# Sheet1.net
KiCad netlist of a schematic drawn in Altium Designer
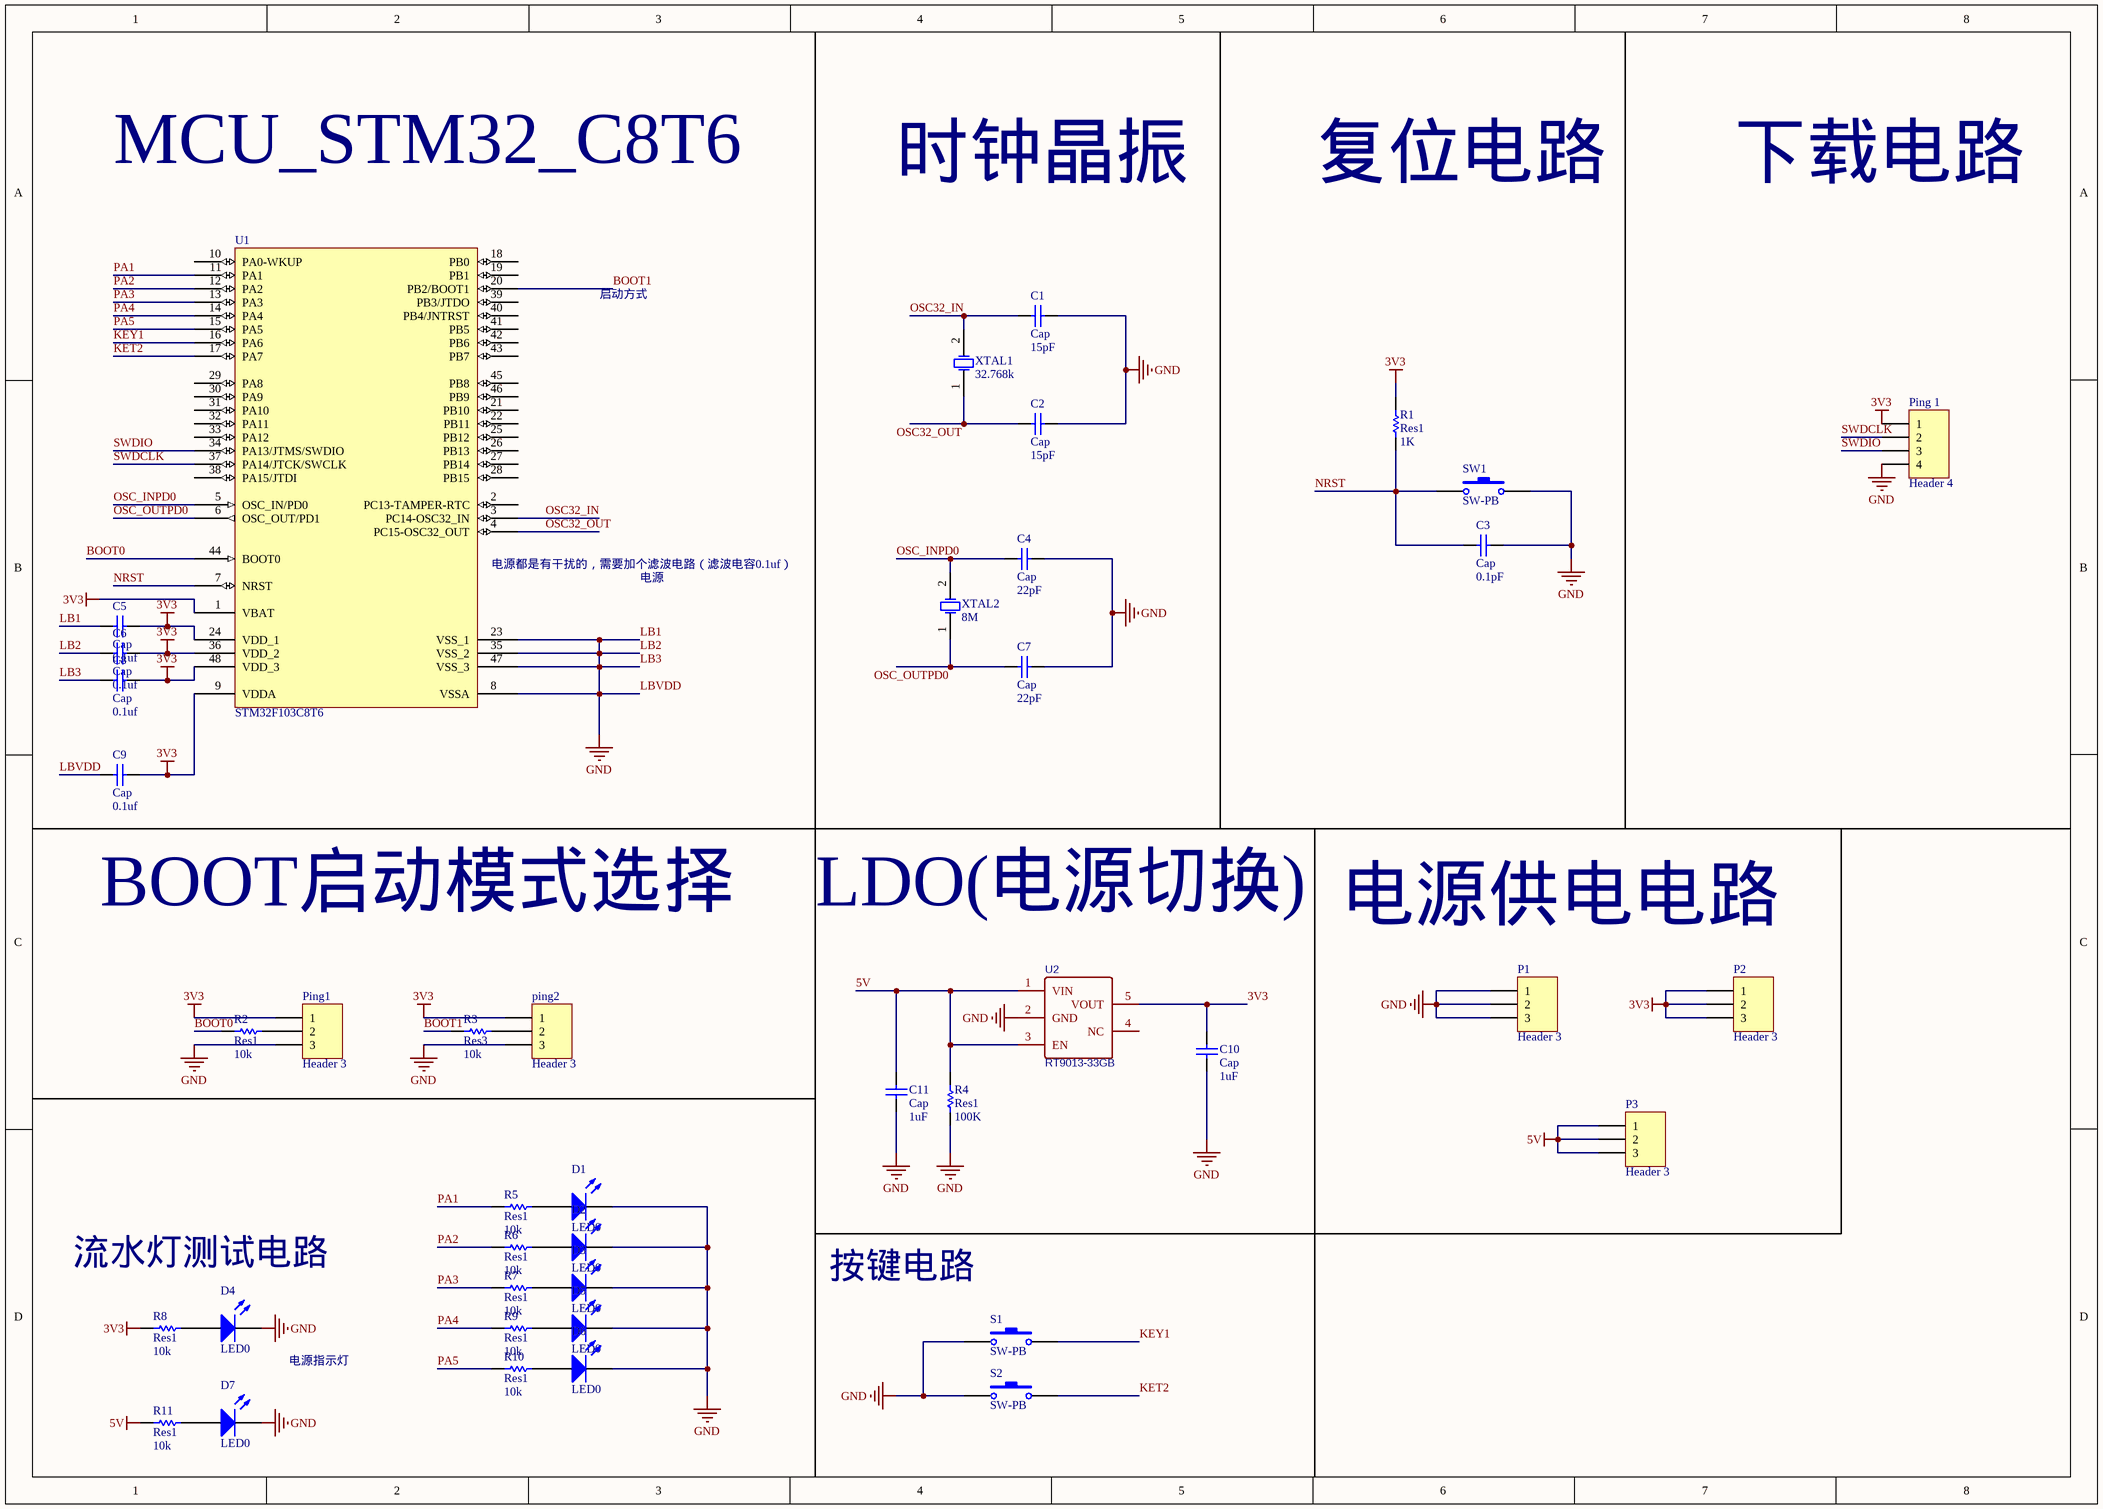
[diagram p0: Sheet1.SchDoc]

(export (version "E")
  (design (tool "Eeschema 10.0.6"))
  (components
    (comp (ref "C1")
      (value "Cap")
      (footprint "RAD-0.3")
      (description "Capacitor")
      (fields (field (name "ALTIUM_VALUE") "15pF") (field (name "PUBLISHER") "Altium Limited"))
      (libsource (lib "Miscellaneous Devices") (part "Cap"))
    )
    (comp (ref "C2")
      (value "Cap")
      (footprint "RAD-0.3")
      (description "Capacitor")
      (fields (field (name "ALTIUM_VALUE") "15pF") (field (name "PUBLISHER") "Altium Limited"))
      (libsource (lib "Miscellaneous Devices") (part "Cap"))
    )
    (comp (ref "C3")
      (value "Cap")
      (footprint "RAD-0.3")
      (description "Capacitor")
      (fields (field (name "ALTIUM_VALUE") "0.1pF") (field (name "PUBLISHER") "Altium Limited"))
      (libsource (lib "Miscellaneous Devices") (part "Cap"))
    )
    (comp (ref "C4")
      (value "Cap")
      (footprint "RAD-0.3")
      (description "Capacitor")
      (fields (field (name "ALTIUM_VALUE") "22pF") (field (name "PUBLISHER") "Altium Limited"))
      (libsource (lib "Miscellaneous Devices") (part "Cap"))
    )
    (comp (ref "C5")
      (value "Cap")
      (footprint "RAD-0.3")
      (description "Capacitor")
      (fields (field (name "ALTIUM_VALUE") "0.1uf") (field (name "PUBLISHER") "Altium Limited"))
      (libsource (lib "Miscellaneous Devices") (part "Cap"))
    )
    (comp (ref "C6")
      (value "Cap")
      (footprint "RAD-0.3")
      (description "Capacitor")
      (fields (field (name "ALTIUM_VALUE") "0.1uf") (field (name "PUBLISHER") "Altium Limited"))
      (libsource (lib "Miscellaneous Devices") (part "Cap"))
    )
    (comp (ref "C7")
      (value "Cap")
      (footprint "RAD-0.3")
      (description "Capacitor")
      (fields (field (name "ALTIUM_VALUE") "22pF") (field (name "PUBLISHER") "Altium Limited"))
      (libsource (lib "Miscellaneous Devices") (part "Cap"))
    )
    (comp (ref "C8")
      (value "Cap")
      (footprint "RAD-0.3")
      (description "Capacitor")
      (fields (field (name "ALTIUM_VALUE") "0.1uf") (field (name "PUBLISHER") "Altium Limited"))
      (libsource (lib "Miscellaneous Devices") (part "Cap"))
    )
    (comp (ref "C9")
      (value "Cap")
      (footprint "RAD-0.3")
      (description "Capacitor")
      (fields (field (name "ALTIUM_VALUE") "0.1uf") (field (name "PUBLISHER") "Altium Limited"))
      (libsource (lib "Miscellaneous Devices") (part "Cap"))
    )
    (comp (ref "C10")
      (value "Cap")
      (footprint "RAD-0.3")
      (description "Capacitor")
      (fields (field (name "ALTIUM_VALUE") "1uF") (field (name "PUBLISHER") "Altium Limited"))
      (libsource (lib "Miscellaneous Devices") (part "Cap"))
    )
    (comp (ref "C11")
      (value "Cap")
      (footprint "RAD-0.3")
      (description "Capacitor")
      (fields (field (name "ALTIUM_VALUE") "1uF") (field (name "PUBLISHER") "Altium Limited"))
      (libsource (lib "Miscellaneous Devices") (part "Cap"))
    )
    (comp (ref "D1")
      (value "LED0")
      (footprint "LED-0")
      (description "Typical INFRARED GaAs LED")
      (fields (field (name "PUBLISHER") "Altium Limited"))
      (libsource (lib "Miscellaneous Devices") (part "LED0"))
    )
    (comp (ref "D2")
      (value "LED0")
      (footprint "LED-0")
      (description "Typical INFRARED GaAs LED")
      (fields (field (name "PUBLISHER") "Altium Limited"))
      (libsource (lib "Miscellaneous Devices") (part "LED0"))
    )
    (comp (ref "D3")
      (value "LED0")
      (footprint "LED-0")
      (description "Typical INFRARED GaAs LED")
      (fields (field (name "PUBLISHER") "Altium Limited"))
      (libsource (lib "Miscellaneous Devices") (part "LED0"))
    )
    (comp (ref "D4")
      (value "LED0")
      (footprint "LED-0")
      (description "Typical INFRARED GaAs LED")
      (fields (field (name "PUBLISHER") "Altium Limited"))
      (libsource (lib "Miscellaneous Devices") (part "LED0"))
    )
    (comp (ref "D5")
      (value "LED0")
      (footprint "LED-0")
      (description "Typical INFRARED GaAs LED")
      (fields (field (name "PUBLISHER") "Altium Limited"))
      (libsource (lib "Miscellaneous Devices") (part "LED0"))
    )
    (comp (ref "D6")
      (value "LED0")
      (footprint "LED-0")
      (description "Typical INFRARED GaAs LED")
      (fields (field (name "PUBLISHER") "Altium Limited"))
      (libsource (lib "Miscellaneous Devices") (part "LED0"))
    )
    (comp (ref "D7")
      (value "LED0")
      (footprint "LED-0")
      (description "Typical INFRARED GaAs LED")
      (fields (field (name "PUBLISHER") "Altium Limited"))
      (libsource (lib "Miscellaneous Devices") (part "LED0"))
    )
    (comp (ref "P1")
      (value "Header 3")
      (footprint "HDR1X3")
      (description "Header, 3-Pin")
      (fields (field (name "PUBLISHER") "Altium Limited"))
      (libsource (lib "Miscellaneous Connectors") (part "Header 3"))
    )
    (comp (ref "P2")
      (value "Header 3")
      (footprint "HDR1X3")
      (description "Header, 3-Pin")
      (fields (field (name "PUBLISHER") "Altium Limited"))
      (libsource (lib "Miscellaneous Connectors") (part "Header 3"))
    )
    (comp (ref "P3")
      (value "Header 3")
      (footprint "HDR1X3")
      (description "Header, 3-Pin")
      (fields (field (name "PUBLISHER") "Altium Limited"))
      (libsource (lib "Miscellaneous Connectors") (part "Header 3"))
    )
    (comp (ref "Ping 1")
      (value "Header 4")
      (footprint "HDR1X4")
      (description "Header, 4-Pin")
      (fields (field (name "PUBLISHER") "Altium Limited"))
      (libsource (lib "Miscellaneous Connectors") (part "Header 4"))
    )
    (comp (ref "Ping1")
      (value "Header 3")
      (footprint "HDR1X3")
      (description "Header, 3-Pin")
      (fields (field (name "PUBLISHER") "Altium Limited"))
      (libsource (lib "Miscellaneous Connectors") (part "Header 3"))
    )
    (comp (ref "ping2")
      (value "Header 3")
      (footprint "HDR1X3")
      (description "Header, 3-Pin")
      (fields (field (name "PUBLISHER") "Altium Limited"))
      (libsource (lib "Miscellaneous Connectors") (part "Header 3"))
    )
    (comp (ref "R1")
      (value "Res1")
      (footprint "AXIAL-0.3")
      (description "Resistor")
      (fields (field (name "ALTIUM_VALUE") "1K") (field (name "PUBLISHER") "Altium Limited"))
      (libsource (lib "Miscellaneous Devices") (part "Res1"))
    )
    (comp (ref "R2")
      (value "Res1")
      (footprint "AXIAL-0.3")
      (description "Resistor")
      (fields (field (name "ALTIUM_VALUE") "10k") (field (name "PUBLISHER") "Altium Limited"))
      (libsource (lib "Miscellaneous Devices") (part "Res1"))
    )
    (comp (ref "R3")
      (value "Res3")
      (footprint "AXIAL-0.3")
      (description "Resistor")
      (fields (field (name "ALTIUM_VALUE") "10k") (field (name "PUBLISHER") "Altium Limited"))
      (libsource (lib "Miscellaneous Devices") (part "Res1"))
    )
    (comp (ref "R4")
      (value "Res1")
      (footprint "AXIAL-0.3")
      (description "Resistor")
      (fields (field (name "ALTIUM_VALUE") "100K") (field (name "PUBLISHER") "Altium Limited"))
      (libsource (lib "Miscellaneous Devices") (part "Res1"))
    )
    (comp (ref "R5")
      (value "Res1")
      (footprint "AXIAL-0.3")
      (description "Resistor")
      (fields (field (name "ALTIUM_VALUE") "10k") (field (name "PUBLISHER") "Altium Limited"))
      (libsource (lib "Miscellaneous Devices") (part "Res1"))
    )
    (comp (ref "R6")
      (value "Res1")
      (footprint "AXIAL-0.3")
      (description "Resistor")
      (fields (field (name "ALTIUM_VALUE") "10k") (field (name "PUBLISHER") "Altium Limited"))
      (libsource (lib "Miscellaneous Devices") (part "Res1"))
    )
    (comp (ref "R7")
      (value "Res1")
      (footprint "AXIAL-0.3")
      (description "Resistor")
      (fields (field (name "ALTIUM_VALUE") "10k") (field (name "PUBLISHER") "Altium Limited"))
      (libsource (lib "Miscellaneous Devices") (part "Res1"))
    )
    (comp (ref "R8")
      (value "Res1")
      (footprint "AXIAL-0.3")
      (description "Resistor")
      (fields (field (name "ALTIUM_VALUE") "10k") (field (name "PUBLISHER") "Altium Limited"))
      (libsource (lib "Miscellaneous Devices") (part "Res1"))
    )
    (comp (ref "R9")
      (value "Res1")
      (footprint "AXIAL-0.3")
      (description "Resistor")
      (fields (field (name "ALTIUM_VALUE") "10k") (field (name "PUBLISHER") "Altium Limited"))
      (libsource (lib "Miscellaneous Devices") (part "Res1"))
    )
    (comp (ref "R10")
      (value "Res1")
      (footprint "AXIAL-0.3")
      (description "Resistor")
      (fields (field (name "ALTIUM_VALUE") "10k") (field (name "PUBLISHER") "Altium Limited"))
      (libsource (lib "Miscellaneous Devices") (part "Res1"))
    )
    (comp (ref "R11")
      (value "Res1")
      (footprint "AXIAL-0.3")
      (description "Resistor")
      (fields (field (name "ALTIUM_VALUE") "10k") (field (name "PUBLISHER") "Altium Limited"))
      (libsource (lib "Miscellaneous Devices") (part "Res1"))
    )
    (comp (ref "S1")
      (value "SW-PB")
      (footprint "SPST-2")
      (description "Switch")
      (fields (field (name "PUBLISHER") "Altium Limited"))
      (libsource (lib "Miscellaneous Devices") (part "SW-PB"))
    )
    (comp (ref "S2")
      (value "SW-PB")
      (footprint "SPST-2")
      (description "Switch")
      (fields (field (name "PUBLISHER") "Altium Limited"))
      (libsource (lib "Miscellaneous Devices") (part "SW-PB"))
    )
    (comp (ref "SW1")
      (value "SW-PB")
      (footprint "SPST-2")
      (description "Switch")
      (fields (field (name "PUBLISHER") "Altium Limited"))
      (libsource (lib "Miscellaneous Devices") (part "SW-PB"))
    )
    (comp (ref "U1")
      (value "STM32F103C8T6")
      (footprint "LQFP48_N")
      (description "STM32 ARM-based 32-bit MCU with 64 Kbytes Flash, 48-pin LQFP, Industrial Temperature")
      (fields (field (name "PUBLISHER") "Altium Limited"))
      (libsource (lib "ST Microcontroller 32-Bit STM32") (part "STM32F103C8T6"))
    )
    (comp (ref "U2")
      (value "RT9013-33GB")
      (footprint "SOT-23-5_L3.0-W1.7-P0.95-LS2.8-BR")
      (fields (field (name "BOM_SUPPLIER PART") "C47773"))
      (libsource (lib "RT9013-33G") (part "RT9013-33GB"))
    )
    (comp (ref "XTAL1")
      (value "32.768k")
      (footprint "R38")
      (description "Crystal Oscillator")
      (fields (field (name "PUBLISHER") "Altium Limited"))
      (libsource (lib "Miscellaneous Devices") (part "XTAL"))
    )
    (comp (ref "XTAL2")
      (value "8M")
      (footprint "R38")
      (description "Crystal Oscillator")
      (fields (field (name "PUBLISHER") "Altium Limited"))
      (libsource (lib "Miscellaneous Devices") (part "XTAL"))
    )
  )
  (nets
    (net (code "1") (name "/BOOT0") (class "Default")
      (node (ref "R2") (pin "1") (pinfunction "1_1") (pintype "passive"))
      (node (ref "U1") (pin "44") (pinfunction "BOOT0_44") (pintype "input"))
    )
    (net (code "2") (name "/BOOT1") (class "Default")
      (node (ref "R3") (pin "1") (pinfunction "1_1") (pintype "passive"))
      (node (ref "U1") (pin "20") (pinfunction "PB2/BOOT1_20") (pintype "bidirectional"))
    )
    (net (code "3") (name "/KET2") (class "Default")
      (node (ref "S2") (pin "2") (pinfunction "2_2") (pintype "passive"))
      (node (ref "U1") (pin "17") (pinfunction "PA7_17") (pintype "bidirectional"))
    )
    (net (code "4") (name "/KEY1") (class "Default")
      (node (ref "S1") (pin "2") (pinfunction "2_2") (pintype "passive"))
      (node (ref "U1") (pin "16") (pinfunction "PA6_16") (pintype "bidirectional"))
    )
    (net (code "5") (name "/NRST") (class "Default")
      (node (ref "C3") (pin "1") (pinfunction "1_1") (pintype "passive"))
      (node (ref "R1") (pin "1") (pinfunction "1_1") (pintype "passive"))
      (node (ref "SW1") (pin "1") (pinfunction "1_1") (pintype "passive"))
      (node (ref "U1") (pin "7") (pinfunction "NRST_7") (pintype "bidirectional"))
    )
    (net (code "6") (name "/OSC32_IN") (class "Default")
      (node (ref "C1") (pin "1") (pinfunction "1_1") (pintype "passive"))
      (node (ref "U1") (pin "3") (pinfunction "PC14-OSC32_IN_3") (pintype "bidirectional"))
      (node (ref "XTAL1") (pin "2") (pinfunction "OSC2_2") (pintype "passive"))
    )
    (net (code "7") (name "/OSC32_OUT") (class "Default")
      (node (ref "C2") (pin "2") (pinfunction "2_2") (pintype "passive"))
      (node (ref "U1") (pin "4") (pinfunction "PC15-OSC32_OUT_4") (pintype "bidirectional"))
      (node (ref "XTAL1") (pin "1") (pinfunction "OSC1_1") (pintype "passive"))
    )
    (net (code "8") (name "/OSC_INPD0") (class "Default")
      (node (ref "C4") (pin "1") (pinfunction "1_1") (pintype "passive"))
      (node (ref "U1") (pin "5") (pinfunction "OSC_IN/PD0_5") (pintype "input"))
      (node (ref "XTAL2") (pin "2") (pinfunction "OSC2_2") (pintype "passive"))
    )
    (net (code "9") (name "/OSC_OUTPD0") (class "Default")
      (node (ref "C7") (pin "2") (pinfunction "2_2") (pintype "passive"))
      (node (ref "U1") (pin "6") (pinfunction "OSC_OUT/PD1_6") (pintype "output"))
      (node (ref "XTAL2") (pin "1") (pinfunction "OSC1_1") (pintype "passive"))
    )
    (net (code "10") (name "/PA1") (class "Default")
      (node (ref "R5") (pin "1") (pinfunction "1_1") (pintype "passive"))
      (node (ref "U1") (pin "11") (pinfunction "PA1_11") (pintype "bidirectional"))
    )
    (net (code "11") (name "/PA2") (class "Default")
      (node (ref "R6") (pin "1") (pinfunction "1_1") (pintype "passive"))
      (node (ref "U1") (pin "12") (pinfunction "PA2_12") (pintype "bidirectional"))
    )
    (net (code "12") (name "/PA3") (class "Default")
      (node (ref "R7") (pin "1") (pinfunction "1_1") (pintype "passive"))
      (node (ref "U1") (pin "13") (pinfunction "PA3_13") (pintype "bidirectional"))
    )
    (net (code "13") (name "/PA4") (class "Default")
      (node (ref "R9") (pin "1") (pinfunction "1_1") (pintype "passive"))
      (node (ref "U1") (pin "14") (pinfunction "PA4_14") (pintype "bidirectional"))
    )
    (net (code "14") (name "/PA5") (class "Default")
      (node (ref "R10") (pin "1") (pinfunction "1_1") (pintype "passive"))
      (node (ref "U1") (pin "15") (pinfunction "PA5_15") (pintype "bidirectional"))
    )
    (net (code "15") (name "/SWDCLK") (class "Default")
      (node (ref "Ping 1") (pin "2") (pinfunction "2_2") (pintype "passive"))
      (node (ref "U1") (pin "37") (pinfunction "PA14/JTCK/SWCLK_37") (pintype "bidirectional"))
    )
    (net (code "16") (name "/SWDIO") (class "Default")
      (node (ref "Ping 1") (pin "3") (pinfunction "3_3") (pintype "passive"))
      (node (ref "U1") (pin "34") (pinfunction "PA13/JTMS/SWDIO_34") (pintype "bidirectional"))
    )
    (net (code "17") (name "3V3") (class "Default")
      (node (ref "C10") (pin "2") (pinfunction "2_2") (pintype "passive"))
      (node (ref "C5") (pin "2") (pinfunction "2_2") (pintype "passive"))
      (node (ref "C6") (pin "2") (pinfunction "2_2") (pintype "passive"))
      (node (ref "C8") (pin "2") (pinfunction "2_2") (pintype "passive"))
      (node (ref "C9") (pin "2") (pinfunction "2_2") (pintype "passive"))
      (node (ref "P2") (pin "1") (pinfunction "1_1") (pintype "passive"))
      (node (ref "P2") (pin "2") (pinfunction "2_2") (pintype "passive"))
      (node (ref "P2") (pin "3") (pinfunction "3_3") (pintype "passive"))
      (node (ref "Ping 1") (pin "1") (pinfunction "1_1") (pintype "passive"))
      (node (ref "Ping1") (pin "1") (pinfunction "1_1") (pintype "passive"))
      (node (ref "R1") (pin "2") (pinfunction "2_2") (pintype "passive"))
      (node (ref "R8") (pin "1") (pinfunction "1_1") (pintype "passive"))
      (node (ref "U1") (pin "1") (pinfunction "VBAT_1") (pintype "power_in"))
      (node (ref "U1") (pin "24") (pinfunction "VDD_1_24") (pintype "power_in"))
      (node (ref "U1") (pin "36") (pinfunction "VDD_2_36") (pintype "power_in"))
      (node (ref "U1") (pin "48") (pinfunction "VDD_3_48") (pintype "power_in"))
      (node (ref "U1") (pin "9") (pinfunction "VDDA_9") (pintype "power_in"))
      (node (ref "U2") (pin "5") (pinfunction "VOUT_5") (pintype "passive"))
      (node (ref "ping2") (pin "1") (pinfunction "1_1") (pintype "passive"))
    )
    (net (code "18") (name "5V") (class "Default")
      (node (ref "C11") (pin "2") (pinfunction "2_2") (pintype "passive"))
      (node (ref "P3") (pin "1") (pinfunction "1_1") (pintype "passive"))
      (node (ref "P3") (pin "2") (pinfunction "2_2") (pintype "passive"))
      (node (ref "P3") (pin "3") (pinfunction "3_3") (pintype "passive"))
      (node (ref "R11") (pin "1") (pinfunction "1_1") (pintype "passive"))
      (node (ref "R4") (pin "2") (pinfunction "2_2") (pintype "passive"))
      (node (ref "U2") (pin "1") (pinfunction "VIN_1") (pintype "passive"))
      (node (ref "U2") (pin "3") (pinfunction "EN_3") (pintype "passive"))
    )
    (net (code "19") (name "GND") (class "Default")
      (node (ref "C1") (pin "2") (pinfunction "2_2") (pintype "passive"))
      (node (ref "C10") (pin "1") (pinfunction "1_1") (pintype "passive"))
      (node (ref "C11") (pin "1") (pinfunction "1_1") (pintype "passive"))
      (node (ref "C2") (pin "1") (pinfunction "1_1") (pintype "passive"))
      (node (ref "C3") (pin "2") (pinfunction "2_2") (pintype "passive"))
      (node (ref "C4") (pin "2") (pinfunction "2_2") (pintype "passive"))
      (node (ref "C5") (pin "1") (pinfunction "1_1") (pintype "passive"))
      (node (ref "C6") (pin "1") (pinfunction "1_1") (pintype "passive"))
      (node (ref "C7") (pin "1") (pinfunction "1_1") (pintype "passive"))
      (node (ref "C8") (pin "1") (pinfunction "1_1") (pintype "passive"))
      (node (ref "C9") (pin "1") (pinfunction "1_1") (pintype "passive"))
      (node (ref "D1") (pin "2") (pinfunction "K_2") (pintype "passive"))
      (node (ref "D2") (pin "2") (pinfunction "K_2") (pintype "passive"))
      (node (ref "D3") (pin "2") (pinfunction "K_2") (pintype "passive"))
      (node (ref "D4") (pin "2") (pinfunction "K_2") (pintype "passive"))
      (node (ref "D5") (pin "2") (pinfunction "K_2") (pintype "passive"))
      (node (ref "D6") (pin "2") (pinfunction "K_2") (pintype "passive"))
      (node (ref "D7") (pin "2") (pinfunction "K_2") (pintype "passive"))
      (node (ref "P1") (pin "1") (pinfunction "1_1") (pintype "passive"))
      (node (ref "P1") (pin "2") (pinfunction "2_2") (pintype "passive"))
      (node (ref "P1") (pin "3") (pinfunction "3_3") (pintype "passive"))
      (node (ref "Ping 1") (pin "4") (pinfunction "4_4") (pintype "passive"))
      (node (ref "Ping1") (pin "3") (pinfunction "3_3") (pintype "passive"))
      (node (ref "R4") (pin "1") (pinfunction "1_1") (pintype "passive"))
      (node (ref "S1") (pin "1") (pinfunction "1_1") (pintype "passive"))
      (node (ref "S2") (pin "1") (pinfunction "1_1") (pintype "passive"))
      (node (ref "SW1") (pin "2") (pinfunction "2_2") (pintype "passive"))
      (node (ref "U1") (pin "23") (pinfunction "VSS_1_23") (pintype "power_in"))
      (node (ref "U1") (pin "35") (pinfunction "VSS_2_35") (pintype "power_in"))
      (node (ref "U1") (pin "47") (pinfunction "VSS_3_47") (pintype "power_in"))
      (node (ref "U1") (pin "8") (pinfunction "VSSA_8") (pintype "power_in"))
      (node (ref "U2") (pin "2") (pinfunction "GND_2") (pintype "passive"))
      (node (ref "ping2") (pin "3") (pinfunction "3_3") (pintype "passive"))
    )
    (net (code "20") (name "Net-(D1-A)") (class "Default")
      (node (ref "D1") (pin "1") (pinfunction "A_1") (pintype "passive"))
      (node (ref "R5") (pin "2") (pinfunction "2_2") (pintype "passive"))
    )
    (net (code "21") (name "Net-(D2-A)") (class "Default")
      (node (ref "D2") (pin "1") (pinfunction "A_1") (pintype "passive"))
      (node (ref "R6") (pin "2") (pinfunction "2_2") (pintype "passive"))
    )
    (net (code "22") (name "Net-(D3-A)") (class "Default")
      (node (ref "D3") (pin "1") (pinfunction "A_1") (pintype "passive"))
      (node (ref "R7") (pin "2") (pinfunction "2_2") (pintype "passive"))
    )
    (net (code "23") (name "Net-(D4-A)") (class "Default")
      (node (ref "D4") (pin "1") (pinfunction "A_1") (pintype "passive"))
      (node (ref "R8") (pin "2") (pinfunction "2_2") (pintype "passive"))
    )
    (net (code "24") (name "Net-(D5-A)") (class "Default")
      (node (ref "D5") (pin "1") (pinfunction "A_1") (pintype "passive"))
      (node (ref "R9") (pin "2") (pinfunction "2_2") (pintype "passive"))
    )
    (net (code "25") (name "Net-(D6-A)") (class "Default")
      (node (ref "D6") (pin "1") (pinfunction "A_1") (pintype "passive"))
      (node (ref "R10") (pin "2") (pinfunction "2_2") (pintype "passive"))
    )
    (net (code "26") (name "Net-(D7-A)") (class "Default")
      (node (ref "D7") (pin "1") (pinfunction "A_1") (pintype "passive"))
      (node (ref "R11") (pin "2") (pinfunction "2_2") (pintype "passive"))
    )
    (net (code "27") (name "Net-(Ping1-Pad2)") (class "Default")
      (node (ref "Ping1") (pin "2") (pinfunction "2_2") (pintype "passive"))
      (node (ref "R2") (pin "2") (pinfunction "2_2") (pintype "passive"))
    )
    (net (code "28") (name "Net-(R3-Pad2)") (class "Default")
      (node (ref "R3") (pin "2") (pinfunction "2_2") (pintype "passive"))
      (node (ref "ping2") (pin "2") (pinfunction "2_2") (pintype "passive"))
    )
    (net (code "29") (name "unconnected-(U1-PA0-WKUP-Pad10)") (class "Default")
      (node (ref "U1") (pin "10") (pinfunction "PA0-WKUP_10") (pintype "bidirectional"))
    )
    (net (code "30") (name "unconnected-(U1-PA8-Pad29)") (class "Default")
      (node (ref "U1") (pin "29") (pinfunction "PA8_29") (pintype "bidirectional"))
    )
    (net (code "31") (name "unconnected-(U1-PA9-Pad30)") (class "Default")
      (node (ref "U1") (pin "30") (pinfunction "PA9_30") (pintype "bidirectional"))
    )
    (net (code "32") (name "unconnected-(U1-PA10-Pad31)") (class "Default")
      (node (ref "U1") (pin "31") (pinfunction "PA10_31") (pintype "bidirectional"))
    )
    (net (code "33") (name "unconnected-(U1-PA11-Pad32)") (class "Default")
      (node (ref "U1") (pin "32") (pinfunction "PA11_32") (pintype "bidirectional"))
    )
    (net (code "34") (name "unconnected-(U1-PA12-Pad33)") (class "Default")
      (node (ref "U1") (pin "33") (pinfunction "PA12_33") (pintype "bidirectional"))
    )
    (net (code "35") (name "unconnected-(U1-PA15{slash}JTDI-Pad38)") (class "Default")
      (node (ref "U1") (pin "38") (pinfunction "PA15/JTDI_38") (pintype "bidirectional"))
    )
    (net (code "36") (name "unconnected-(U1-PB0-Pad18)") (class "Default")
      (node (ref "U1") (pin "18") (pinfunction "PB0_18") (pintype "bidirectional"))
    )
    (net (code "37") (name "unconnected-(U1-PB1-Pad19)") (class "Default")
      (node (ref "U1") (pin "19") (pinfunction "PB1_19") (pintype "bidirectional"))
    )
    (net (code "38") (name "unconnected-(U1-PB3{slash}JTDO-Pad39)") (class "Default")
      (node (ref "U1") (pin "39") (pinfunction "PB3/JTDO_39") (pintype "bidirectional"))
    )
    (net (code "39") (name "unconnected-(U1-PB4{slash}JNTRST-Pad40)") (class "Default")
      (node (ref "U1") (pin "40") (pinfunction "PB4/JNTRST_40") (pintype "bidirectional"))
    )
    (net (code "40") (name "unconnected-(U1-PB5-Pad41)") (class "Default")
      (node (ref "U1") (pin "41") (pinfunction "PB5_41") (pintype "bidirectional"))
    )
    (net (code "41") (name "unconnected-(U1-PB6-Pad42)") (class "Default")
      (node (ref "U1") (pin "42") (pinfunction "PB6_42") (pintype "bidirectional"))
    )
    (net (code "42") (name "unconnected-(U1-PB7-Pad43)") (class "Default")
      (node (ref "U1") (pin "43") (pinfunction "PB7_43") (pintype "bidirectional"))
    )
    (net (code "43") (name "unconnected-(U1-PB8-Pad45)") (class "Default")
      (node (ref "U1") (pin "45") (pinfunction "PB8_45") (pintype "bidirectional"))
    )
    (net (code "44") (name "unconnected-(U1-PB9-Pad46)") (class "Default")
      (node (ref "U1") (pin "46") (pinfunction "PB9_46") (pintype "bidirectional"))
    )
    (net (code "45") (name "unconnected-(U1-PB10-Pad21)") (class "Default")
      (node (ref "U1") (pin "21") (pinfunction "PB10_21") (pintype "bidirectional"))
    )
    (net (code "46") (name "unconnected-(U1-PB11-Pad22)") (class "Default")
      (node (ref "U1") (pin "22") (pinfunction "PB11_22") (pintype "bidirectional"))
    )
    (net (code "47") (name "unconnected-(U1-PB12-Pad25)") (class "Default")
      (node (ref "U1") (pin "25") (pinfunction "PB12_25") (pintype "bidirectional"))
    )
    (net (code "48") (name "unconnected-(U1-PB13-Pad26)") (class "Default")
      (node (ref "U1") (pin "26") (pinfunction "PB13_26") (pintype "bidirectional"))
    )
    (net (code "49") (name "unconnected-(U1-PB14-Pad27)") (class "Default")
      (node (ref "U1") (pin "27") (pinfunction "PB14_27") (pintype "bidirectional"))
    )
    (net (code "50") (name "unconnected-(U1-PB15-Pad28)") (class "Default")
      (node (ref "U1") (pin "28") (pinfunction "PB15_28") (pintype "bidirectional"))
    )
    (net (code "51") (name "unconnected-(U1-PC13-TAMPER-RTC-Pad2)") (class "Default")
      (node (ref "U1") (pin "2") (pinfunction "PC13-TAMPER-RTC_2") (pintype "bidirectional"))
    )
    (net (code "52") (name "unconnected-(U2-NC-Pad4)") (class "Default")
      (node (ref "U2") (pin "4") (pinfunction "NC_4") (pintype "passive"))
    )
  )
)
